# power_router.net
KiCad netlist of a schematic drawn in EAGLE
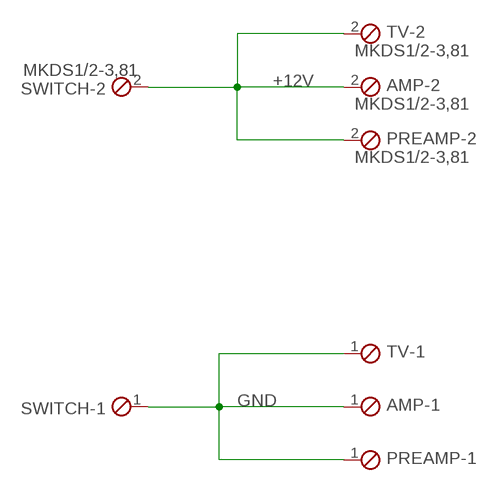
[diagram p0: schematic, sheet 1]

(export (version "E")
  (design (tool "Eeschema 10.0.6"))
  (components
    (comp (ref "AMP")
      (value "MKDS1/2-3,81")
      (footprint "eagle-import:2POL381")
      (libsource (lib "eagle-import") (part "MKDS1/2-3,81"))
    )
    (comp (ref "PREAMP")
      (value "MKDS1/2-3,81")
      (footprint "eagle-import:2POL381")
      (libsource (lib "eagle-import") (part "MKDS1/2-3,81"))
    )
    (comp (ref "SWITCH")
      (value "MKDS1/2-3,81")
      (footprint "eagle-import:2POL381")
      (libsource (lib "eagle-import") (part "MKDS1/2-3,81"))
    )
    (comp (ref "TV")
      (value "MKDS1/2-3,81")
      (footprint "eagle-import:2POL381")
      (libsource (lib "eagle-import") (part "MKDS1/2-3,81"))
    )
  )
  (nets
    (net (code "1") (name "/+12V") (class "Default")
      (node (ref "AMP") (pin "2") (pinfunction "1_2") (pintype "passive"))
      (node (ref "PREAMP") (pin "2") (pinfunction "1_2") (pintype "passive"))
      (node (ref "SWITCH") (pin "2") (pinfunction "1_2") (pintype "passive"))
      (node (ref "TV") (pin "2") (pinfunction "1_2") (pintype "passive"))
    )
    (net (code "2") (name "/GND") (class "Default")
      (node (ref "AMP") (pin "1") (pinfunction "1_1") (pintype "passive"))
      (node (ref "PREAMP") (pin "1") (pinfunction "1_1") (pintype "passive"))
      (node (ref "SWITCH") (pin "1") (pinfunction "1_1") (pintype "passive"))
      (node (ref "TV") (pin "1") (pinfunction "1_1") (pintype "passive"))
    )
  )
)
